# MainPCB_E.net
KiCad netlist of a schematic drawn in EAGLE
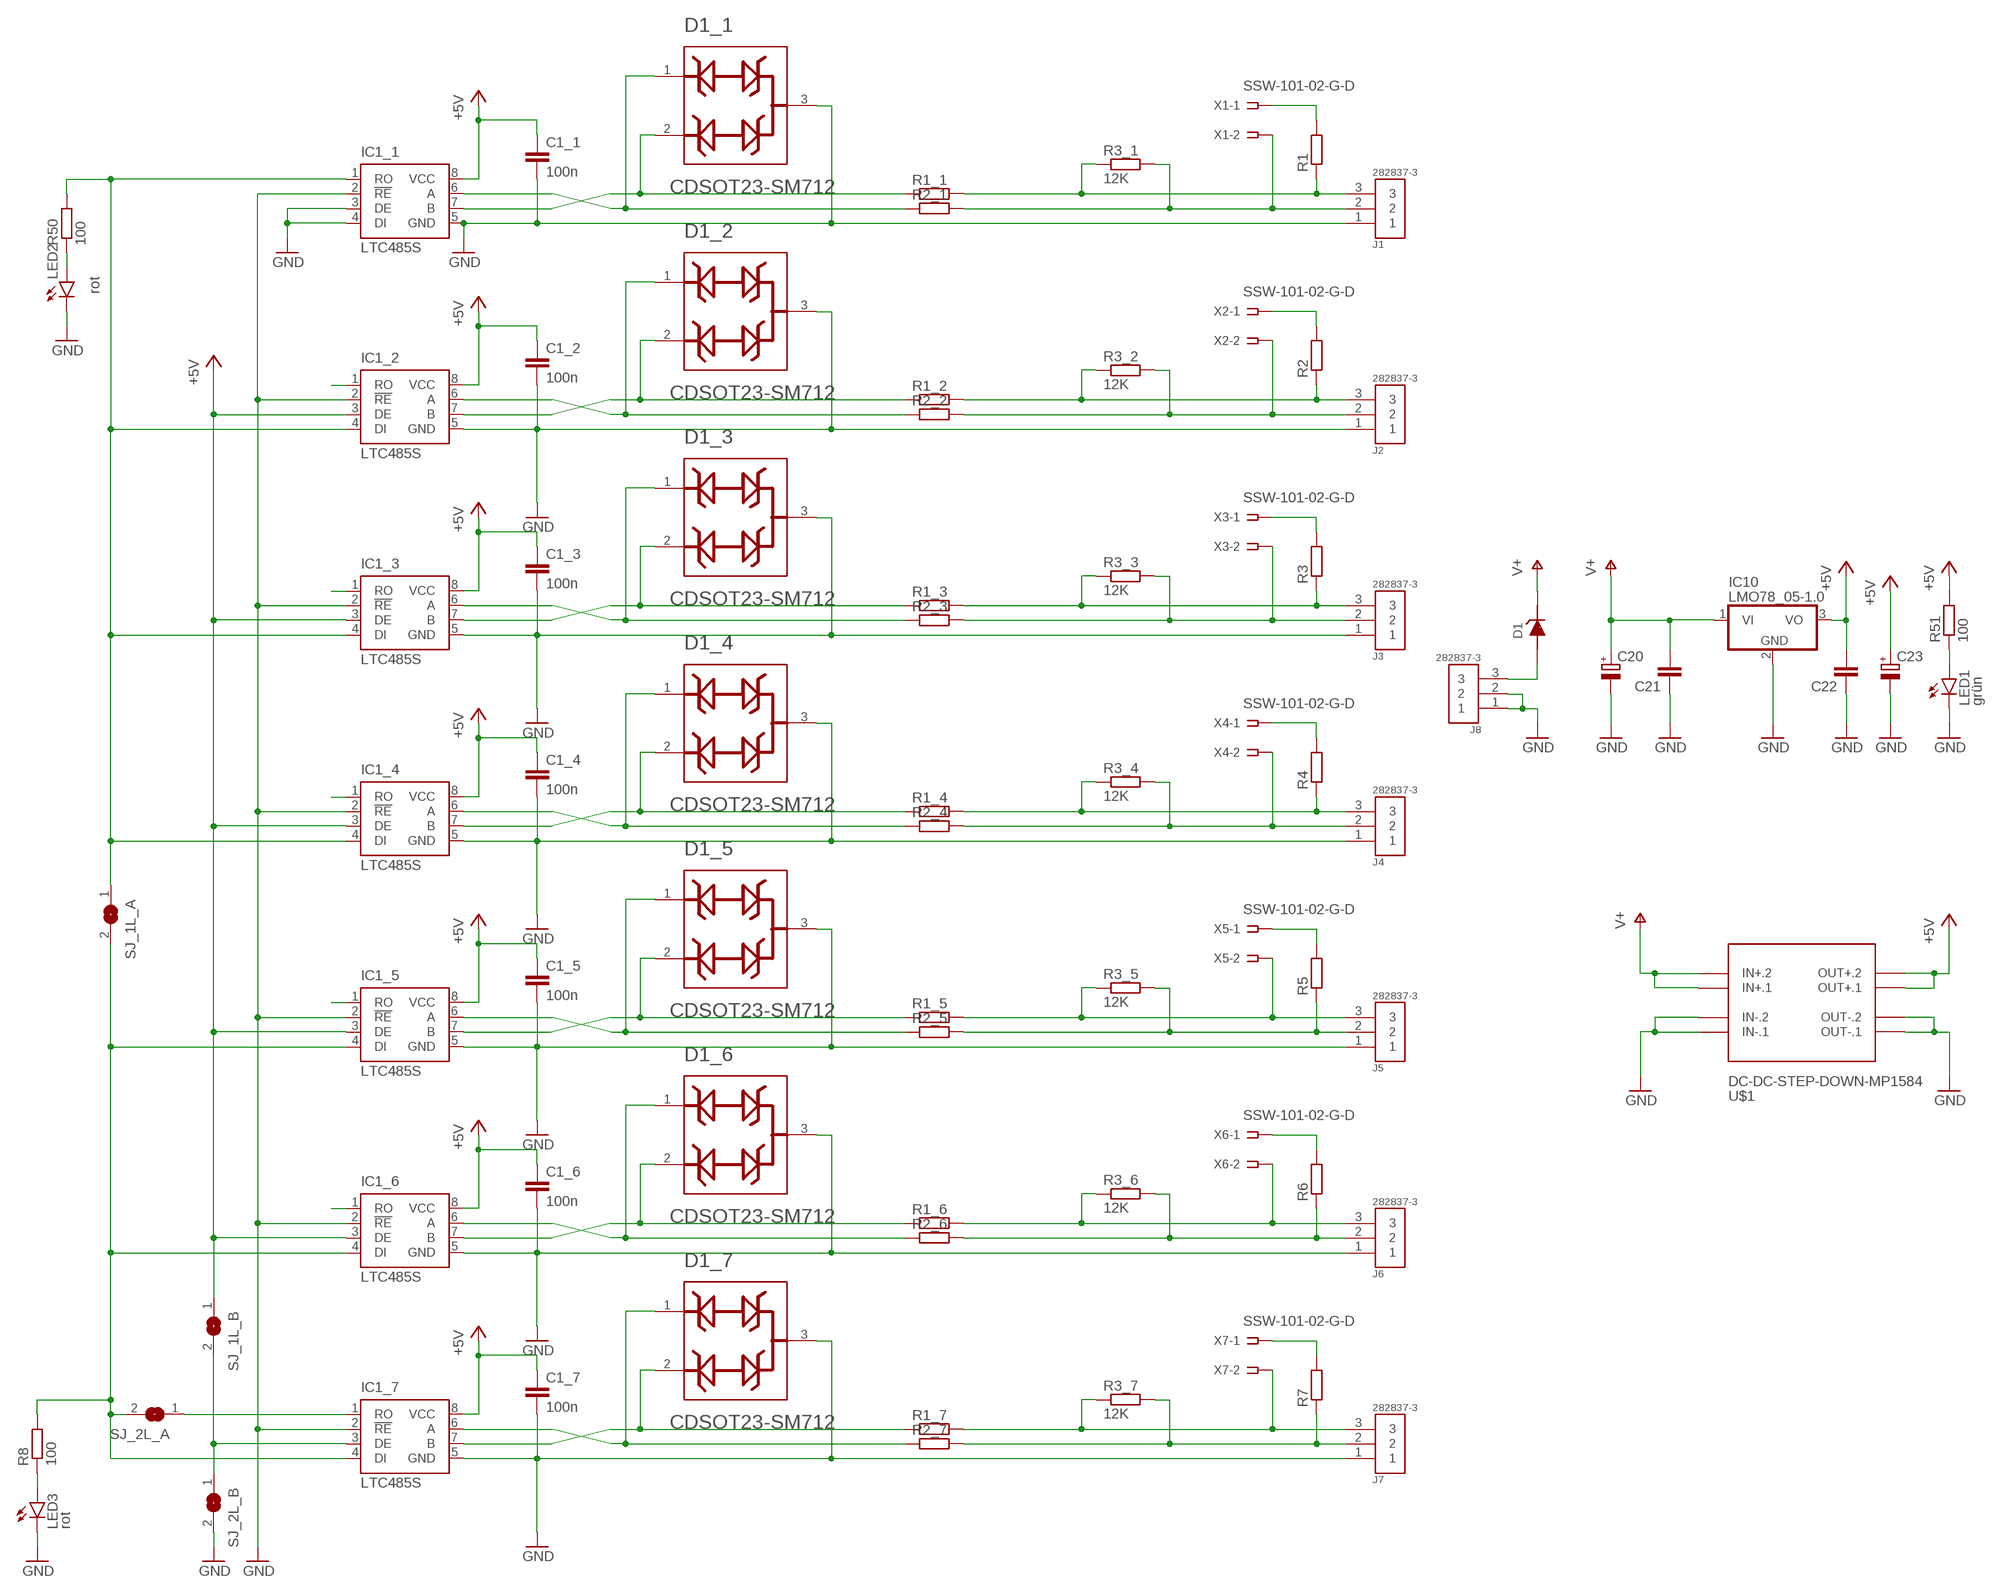
[diagram p0: schematic, sheet 1]

(export (version "E")
  (design (tool "Eeschema 10.0.6"))
  (components
    (comp (ref "C1_1")
      (value "100n")
      (footprint "eagle-import:C0603K")
      (libsource (lib "eagle-import") (part "C-EUC0603K"))
    )
    (comp (ref "C1_2")
      (value "100n")
      (footprint "eagle-import:C0603K")
      (libsource (lib "eagle-import") (part "C-EUC0603K"))
    )
    (comp (ref "C1_3")
      (value "100n")
      (footprint "eagle-import:C0603K")
      (libsource (lib "eagle-import") (part "C-EUC0603K"))
    )
    (comp (ref "C1_4")
      (value "100n")
      (footprint "eagle-import:C0603K")
      (libsource (lib "eagle-import") (part "C-EUC0603K"))
    )
    (comp (ref "C1_5")
      (value "100n")
      (footprint "eagle-import:C0603K")
      (libsource (lib "eagle-import") (part "C-EUC0603K"))
    )
    (comp (ref "C1_6")
      (value "100n")
      (footprint "eagle-import:C0603K")
      (libsource (lib "eagle-import") (part "C-EUC0603K"))
    )
    (comp (ref "C1_7")
      (value "100n")
      (footprint "eagle-import:C0603K")
      (libsource (lib "eagle-import") (part "C-EUC0603K"))
    )
    (comp (ref "C20")
      (value "CPOL-EUE5-8.5")
      (footprint "eagle-import:E5-8,5")
      (libsource (lib "eagle-import") (part "CPOL-EUE5-8.5"))
    )
    (comp (ref "C21")
      (value "C-EUC0805K")
      (footprint "eagle-import:C0805K")
      (libsource (lib "eagle-import") (part "C-EUC0805K"))
    )
    (comp (ref "C22")
      (value "C-EUC0805K")
      (footprint "eagle-import:C0805K")
      (libsource (lib "eagle-import") (part "C-EUC0805K"))
    )
    (comp (ref "C23")
      (value "CPOL-EUE5-8.5")
      (footprint "eagle-import:E5-8,5")
      (libsource (lib "eagle-import") (part "CPOL-EUE5-8.5"))
    )
    (comp (ref "D1")
      (value "ZMM")
      (footprint "eagle-import:MINIMELF")
      (libsource (lib "eagle-import") (part "ZMM"))
    )
    (comp (ref "D1_1")
      (value "BOURNS_INC._CDSOT23-SM712BOURNS_INC._CDSOT23-SM712_0_1")
      (footprint "eagle-import:BOURNS_INC._CDSOT23-SM712_1")
      (fields
        (field (name "DIGIKEY_PART_NUMBER") "CDSOT23-SM712CT-ND")
        (field (name "MF") "Bourns Inc.")
        (field (name "MOUSER_PART_NUMBER") "652-CDSOT23-SM712")
      )
      (libsource (lib "eagle-import") (part "BOURNS_INC._CDSOT23-SM712BOURNS_INC._CDSOT23-SM712_0_1"))
    )
    (comp (ref "D1_2")
      (value "BOURNS_INC._CDSOT23-SM712BOURNS_INC._CDSOT23-SM712_0_1")
      (footprint "eagle-import:BOURNS_INC._CDSOT23-SM712_1")
      (fields
        (field (name "DIGIKEY_PART_NUMBER") "CDSOT23-SM712CT-ND")
        (field (name "MF") "Bourns Inc.")
        (field (name "MOUSER_PART_NUMBER") "652-CDSOT23-SM712")
      )
      (libsource (lib "eagle-import") (part "BOURNS_INC._CDSOT23-SM712BOURNS_INC._CDSOT23-SM712_0_1"))
    )
    (comp (ref "D1_3")
      (value "BOURNS_INC._CDSOT23-SM712BOURNS_INC._CDSOT23-SM712_0_1")
      (footprint "eagle-import:BOURNS_INC._CDSOT23-SM712_1")
      (fields
        (field (name "DIGIKEY_PART_NUMBER") "CDSOT23-SM712CT-ND")
        (field (name "MF") "Bourns Inc.")
        (field (name "MOUSER_PART_NUMBER") "652-CDSOT23-SM712")
      )
      (libsource (lib "eagle-import") (part "BOURNS_INC._CDSOT23-SM712BOURNS_INC._CDSOT23-SM712_0_1"))
    )
    (comp (ref "D1_4")
      (value "BOURNS_INC._CDSOT23-SM712BOURNS_INC._CDSOT23-SM712_0_1")
      (footprint "eagle-import:BOURNS_INC._CDSOT23-SM712_1")
      (fields
        (field (name "DIGIKEY_PART_NUMBER") "CDSOT23-SM712CT-ND")
        (field (name "MF") "Bourns Inc.")
        (field (name "MOUSER_PART_NUMBER") "652-CDSOT23-SM712")
      )
      (libsource (lib "eagle-import") (part "BOURNS_INC._CDSOT23-SM712BOURNS_INC._CDSOT23-SM712_0_1"))
    )
    (comp (ref "D1_5")
      (value "BOURNS_INC._CDSOT23-SM712BOURNS_INC._CDSOT23-SM712_0_1")
      (footprint "eagle-import:BOURNS_INC._CDSOT23-SM712_1")
      (fields
        (field (name "DIGIKEY_PART_NUMBER") "CDSOT23-SM712CT-ND")
        (field (name "MF") "Bourns Inc.")
        (field (name "MOUSER_PART_NUMBER") "652-CDSOT23-SM712")
      )
      (libsource (lib "eagle-import") (part "BOURNS_INC._CDSOT23-SM712BOURNS_INC._CDSOT23-SM712_0_1"))
    )
    (comp (ref "D1_6")
      (value "BOURNS_INC._CDSOT23-SM712BOURNS_INC._CDSOT23-SM712_0_1")
      (footprint "eagle-import:BOURNS_INC._CDSOT23-SM712_1")
      (fields
        (field (name "DIGIKEY_PART_NUMBER") "CDSOT23-SM712CT-ND")
        (field (name "MF") "Bourns Inc.")
        (field (name "MOUSER_PART_NUMBER") "652-CDSOT23-SM712")
      )
      (libsource (lib "eagle-import") (part "BOURNS_INC._CDSOT23-SM712BOURNS_INC._CDSOT23-SM712_0_1"))
    )
    (comp (ref "D1_7")
      (value "BOURNS_INC._CDSOT23-SM712BOURNS_INC._CDSOT23-SM712_0_1")
      (footprint "eagle-import:BOURNS_INC._CDSOT23-SM712_1")
      (fields
        (field (name "DIGIKEY_PART_NUMBER") "CDSOT23-SM712CT-ND")
        (field (name "MF") "Bourns Inc.")
        (field (name "MOUSER_PART_NUMBER") "652-CDSOT23-SM712")
      )
      (libsource (lib "eagle-import") (part "BOURNS_INC._CDSOT23-SM712BOURNS_INC._CDSOT23-SM712_0_1"))
    )
    (comp (ref "IC1_1")
      (value "LTC485S")
      (footprint "eagle-import:SOIC8")
      (libsource (lib "eagle-import") (part "LTC485S"))
    )
    (comp (ref "IC1_2")
      (value "LTC485S")
      (footprint "eagle-import:SOIC8")
      (libsource (lib "eagle-import") (part "LTC485S"))
    )
    (comp (ref "IC1_3")
      (value "LTC485S")
      (footprint "eagle-import:SOIC8")
      (libsource (lib "eagle-import") (part "LTC485S"))
    )
    (comp (ref "IC1_4")
      (value "LTC485S")
      (footprint "eagle-import:SOIC8")
      (libsource (lib "eagle-import") (part "LTC485S"))
    )
    (comp (ref "IC1_5")
      (value "LTC485S")
      (footprint "eagle-import:SOIC8")
      (libsource (lib "eagle-import") (part "LTC485S"))
    )
    (comp (ref "IC1_6")
      (value "LTC485S")
      (footprint "eagle-import:SOIC8")
      (libsource (lib "eagle-import") (part "LTC485S"))
    )
    (comp (ref "IC1_7")
      (value "LTC485S")
      (footprint "eagle-import:SOIC8")
      (libsource (lib "eagle-import") (part "LTC485S"))
    )
    (comp (ref "IC10")
      (value "LMO78_05-1.0")
      (footprint "eagle-import:TO220V")
      (libsource (lib "eagle-import") (part "78TV15"))
    )
    (comp (ref "J1")
      (value "282837-3")
      (footprint "eagle-import:TE_282837-3")
      (fields (field (name "MANUFACTURER") "TE CONNECTIVITY"))
      (libsource (lib "eagle-import") (part "282837-3"))
    )
    (comp (ref "J2")
      (value "282837-3")
      (footprint "eagle-import:TE_282837-3")
      (fields (field (name "MANUFACTURER") "TE CONNECTIVITY"))
      (libsource (lib "eagle-import") (part "282837-3"))
    )
    (comp (ref "J3")
      (value "282837-3")
      (footprint "eagle-import:TE_282837-3")
      (fields (field (name "MANUFACTURER") "TE CONNECTIVITY"))
      (libsource (lib "eagle-import") (part "282837-3"))
    )
    (comp (ref "J4")
      (value "282837-3")
      (footprint "eagle-import:TE_282837-3")
      (fields (field (name "MANUFACTURER") "TE CONNECTIVITY"))
      (libsource (lib "eagle-import") (part "282837-3"))
    )
    (comp (ref "J5")
      (value "282837-3")
      (footprint "eagle-import:TE_282837-3")
      (fields (field (name "MANUFACTURER") "TE CONNECTIVITY"))
      (libsource (lib "eagle-import") (part "282837-3"))
    )
    (comp (ref "J6")
      (value "282837-3")
      (footprint "eagle-import:TE_282837-3")
      (fields (field (name "MANUFACTURER") "TE CONNECTIVITY"))
      (libsource (lib "eagle-import") (part "282837-3"))
    )
    (comp (ref "J7")
      (value "282837-3")
      (footprint "eagle-import:TE_282837-3")
      (fields (field (name "MANUFACTURER") "TE CONNECTIVITY"))
      (libsource (lib "eagle-import") (part "282837-3"))
    )
    (comp (ref "J8")
      (value "282837-3")
      (footprint "eagle-import:TE_282837-3")
      (fields (field (name "MANUFACTURER") "TE CONNECTIVITY"))
      (libsource (lib "eagle-import") (part "282837-3"))
    )
    (comp (ref "LED1")
      (value "grün")
      (footprint "eagle-import:LED5MM")
      (libsource (lib "eagle-import") (part "LED5MM"))
    )
    (comp (ref "LED2")
      (value "rot")
      (footprint "eagle-import:LED5MM")
      (libsource (lib "eagle-import") (part "LED5MM"))
    )
    (comp (ref "LED3")
      (value "rot")
      (footprint "eagle-import:LED5MM")
      (libsource (lib "eagle-import") (part "LED5MM"))
    )
    (comp (ref "R1")
      (value "R-EU_R1206")
      (footprint "eagle-import:R1206")
      (libsource (lib "eagle-import") (part "R-EU_R1206"))
    )
    (comp (ref "R1_1")
      (value "R-EU_R0805")
      (footprint "eagle-import:R0805")
      (libsource (lib "eagle-import") (part "R-EU_R0805"))
    )
    (comp (ref "R1_2")
      (value "R-EU_R0805")
      (footprint "eagle-import:R0805")
      (libsource (lib "eagle-import") (part "R-EU_R0805"))
    )
    (comp (ref "R1_3")
      (value "R-EU_R0805")
      (footprint "eagle-import:R0805")
      (libsource (lib "eagle-import") (part "R-EU_R0805"))
    )
    (comp (ref "R1_4")
      (value "R-EU_R0805")
      (footprint "eagle-import:R0805")
      (libsource (lib "eagle-import") (part "R-EU_R0805"))
    )
    (comp (ref "R1_5")
      (value "R-EU_R0805")
      (footprint "eagle-import:R0805")
      (libsource (lib "eagle-import") (part "R-EU_R0805"))
    )
    (comp (ref "R1_6")
      (value "R-EU_R0805")
      (footprint "eagle-import:R0805")
      (libsource (lib "eagle-import") (part "R-EU_R0805"))
    )
    (comp (ref "R1_7")
      (value "R-EU_R0805")
      (footprint "eagle-import:R0805")
      (libsource (lib "eagle-import") (part "R-EU_R0805"))
    )
    (comp (ref "R2")
      (value "R-EU_R1206")
      (footprint "eagle-import:R1206")
      (libsource (lib "eagle-import") (part "R-EU_R1206"))
    )
    (comp (ref "R2_1")
      (value "R-EU_R0805")
      (footprint "eagle-import:R0805")
      (libsource (lib "eagle-import") (part "R-EU_R0805"))
    )
    (comp (ref "R2_2")
      (value "R-EU_R0805")
      (footprint "eagle-import:R0805")
      (libsource (lib "eagle-import") (part "R-EU_R0805"))
    )
    (comp (ref "R2_3")
      (value "R-EU_R0805")
      (footprint "eagle-import:R0805")
      (libsource (lib "eagle-import") (part "R-EU_R0805"))
    )
    (comp (ref "R2_4")
      (value "R-EU_R0805")
      (footprint "eagle-import:R0805")
      (libsource (lib "eagle-import") (part "R-EU_R0805"))
    )
    (comp (ref "R2_5")
      (value "R-EU_R0805")
      (footprint "eagle-import:R0805")
      (libsource (lib "eagle-import") (part "R-EU_R0805"))
    )
    (comp (ref "R2_6")
      (value "R-EU_R0805")
      (footprint "eagle-import:R0805")
      (libsource (lib "eagle-import") (part "R-EU_R0805"))
    )
    (comp (ref "R2_7")
      (value "R-EU_R0805")
      (footprint "eagle-import:R0805")
      (libsource (lib "eagle-import") (part "R-EU_R0805"))
    )
    (comp (ref "R3")
      (value "R-EU_R1206")
      (footprint "eagle-import:R1206")
      (libsource (lib "eagle-import") (part "R-EU_R1206"))
    )
    (comp (ref "R3_1")
      (value "12K")
      (footprint "eagle-import:R0603")
      (libsource (lib "eagle-import") (part "R-EU_R0603"))
    )
    (comp (ref "R3_2")
      (value "12K")
      (footprint "eagle-import:R0603")
      (libsource (lib "eagle-import") (part "R-EU_R0603"))
    )
    (comp (ref "R3_3")
      (value "12K")
      (footprint "eagle-import:R0603")
      (libsource (lib "eagle-import") (part "R-EU_R0603"))
    )
    (comp (ref "R3_4")
      (value "12K")
      (footprint "eagle-import:R0603")
      (libsource (lib "eagle-import") (part "R-EU_R0603"))
    )
    (comp (ref "R3_5")
      (value "12K")
      (footprint "eagle-import:R0603")
      (libsource (lib "eagle-import") (part "R-EU_R0603"))
    )
    (comp (ref "R3_6")
      (value "12K")
      (footprint "eagle-import:R0603")
      (libsource (lib "eagle-import") (part "R-EU_R0603"))
    )
    (comp (ref "R3_7")
      (value "12K")
      (footprint "eagle-import:R0603")
      (libsource (lib "eagle-import") (part "R-EU_R0603"))
    )
    (comp (ref "R4")
      (value "R-EU_R1206")
      (footprint "eagle-import:R1206")
      (libsource (lib "eagle-import") (part "R-EU_R1206"))
    )
    (comp (ref "R5")
      (value "R-EU_R1206")
      (footprint "eagle-import:R1206")
      (libsource (lib "eagle-import") (part "R-EU_R1206"))
    )
    (comp (ref "R6")
      (value "R-EU_R1206")
      (footprint "eagle-import:R1206")
      (libsource (lib "eagle-import") (part "R-EU_R1206"))
    )
    (comp (ref "R7")
      (value "R-EU_R1206")
      (footprint "eagle-import:R1206")
      (libsource (lib "eagle-import") (part "R-EU_R1206"))
    )
    (comp (ref "R8")
      (value "100")
      (footprint "eagle-import:R0603")
      (libsource (lib "eagle-import") (part "R-EU_R0603"))
    )
    (comp (ref "R50")
      (value "100")
      (footprint "eagle-import:R0603")
      (libsource (lib "eagle-import") (part "R-EU_R0603"))
    )
    (comp (ref "R51")
      (value "100")
      (footprint "eagle-import:R0603")
      (libsource (lib "eagle-import") (part "R-EU_R0603"))
    )
    (comp (ref "SJ_1L_A")
      (value "SJ")
      (footprint "eagle-import:SJ")
      (libsource (lib "eagle-import") (part "SJ"))
    )
    (comp (ref "SJ_1L_B")
      (value "SJ")
      (footprint "eagle-import:SJ")
      (libsource (lib "eagle-import") (part "SJ"))
    )
    (comp (ref "SJ_2L_A")
      (value "SJ")
      (footprint "eagle-import:SJ")
      (libsource (lib "eagle-import") (part "SJ"))
    )
    (comp (ref "SJ_2L_B")
      (value "SJ")
      (footprint "eagle-import:SJ")
      (libsource (lib "eagle-import") (part "SJ"))
    )
    (comp (ref "U$1")
      (value "DC-DC-STEP-DOWN-MP1584")
      (footprint "eagle-import:DC-DC-STEP-DOWN-MP1584")
      (libsource (lib "eagle-import") (part "DC-DC-STEP-DOWN-MP1584"))
    )
    (comp (ref "X1")
      (value "SSW-101-02-G-D")
      (footprint "eagle-import:SSW-101-02-G-D")
      (fields (field (name "MF") "Samtec Inc."))
      (libsource (lib "eagle-import") (part "SSW-101-02-G-D"))
    )
    (comp (ref "X2")
      (value "SSW-101-02-G-D")
      (footprint "eagle-import:SSW-101-02-G-D")
      (fields (field (name "MF") "Samtec Inc."))
      (libsource (lib "eagle-import") (part "SSW-101-02-G-D"))
    )
    (comp (ref "X3")
      (value "SSW-101-02-G-D")
      (footprint "eagle-import:SSW-101-02-G-D")
      (fields (field (name "MF") "Samtec Inc."))
      (libsource (lib "eagle-import") (part "SSW-101-02-G-D"))
    )
    (comp (ref "X4")
      (value "SSW-101-02-G-D")
      (footprint "eagle-import:SSW-101-02-G-D")
      (fields (field (name "MF") "Samtec Inc."))
      (libsource (lib "eagle-import") (part "SSW-101-02-G-D"))
    )
    (comp (ref "X5")
      (value "SSW-101-02-G-D")
      (footprint "eagle-import:SSW-101-02-G-D")
      (fields (field (name "MF") "Samtec Inc."))
      (libsource (lib "eagle-import") (part "SSW-101-02-G-D"))
    )
    (comp (ref "X6")
      (value "SSW-101-02-G-D")
      (footprint "eagle-import:SSW-101-02-G-D")
      (fields (field (name "MF") "Samtec Inc."))
      (libsource (lib "eagle-import") (part "SSW-101-02-G-D"))
    )
    (comp (ref "X7")
      (value "SSW-101-02-G-D")
      (footprint "eagle-import:SSW-101-02-G-D")
      (fields (field (name "MF") "Samtec Inc."))
      (libsource (lib "eagle-import") (part "SSW-101-02-G-D"))
    )
  )
  (nets
    (net (code "1") (name "+5V") (class "Default")
      (node (ref "C1_1") (pin "1") (pinfunction "1_1") (pintype "passive"))
      (node (ref "C1_2") (pin "1") (pinfunction "1_1") (pintype "passive"))
      (node (ref "C1_3") (pin "1") (pinfunction "1_1") (pintype "passive"))
      (node (ref "C1_4") (pin "1") (pinfunction "1_1") (pintype "passive"))
      (node (ref "C1_5") (pin "1") (pinfunction "1_1") (pintype "passive"))
      (node (ref "C1_6") (pin "1") (pinfunction "1_1") (pintype "passive"))
      (node (ref "C1_7") (pin "1") (pinfunction "1_1") (pintype "passive"))
      (node (ref "C22") (pin "2") (pinfunction "2_2") (pintype "passive"))
      (node (ref "C23") (pin "+") (pinfunction "+_+") (pintype "passive"))
      (node (ref "IC10") (pin "3") (pinfunction "VO_3") (pintype "passive"))
      (node (ref "IC1_1") (pin "8") (pinfunction "VCC_8") (pintype "input"))
      (node (ref "IC1_2") (pin "3") (pinfunction "DE_3") (pintype "input"))
      (node (ref "IC1_2") (pin "8") (pinfunction "VCC_8") (pintype "input"))
      (node (ref "IC1_3") (pin "3") (pinfunction "DE_3") (pintype "input"))
      (node (ref "IC1_3") (pin "8") (pinfunction "VCC_8") (pintype "input"))
      (node (ref "IC1_4") (pin "3") (pinfunction "DE_3") (pintype "input"))
      (node (ref "IC1_4") (pin "8") (pinfunction "VCC_8") (pintype "input"))
      (node (ref "IC1_5") (pin "3") (pinfunction "DE_3") (pintype "input"))
      (node (ref "IC1_5") (pin "8") (pinfunction "VCC_8") (pintype "input"))
      (node (ref "IC1_6") (pin "3") (pinfunction "DE_3") (pintype "input"))
      (node (ref "IC1_6") (pin "8") (pinfunction "VCC_8") (pintype "input"))
      (node (ref "IC1_7") (pin "8") (pinfunction "VCC_8") (pintype "input"))
      (node (ref "R51") (pin "2") (pinfunction "2_2") (pintype "passive"))
      (node (ref "SJ_1L_B") (pin "1") (pinfunction "1_1") (pintype "passive"))
      (node (ref "U$1") (pin "OUT+.1") (pinfunction "OUT+.1_OUT+.1") (pintype "bidirectional"))
      (node (ref "U$1") (pin "OUT+.2") (pinfunction "OUT+.2_OUT+.2") (pintype "bidirectional"))
    )
    (net (code "2") (name "GND") (class "Default")
      (node (ref "C1_1") (pin "2") (pinfunction "2_2") (pintype "passive"))
      (node (ref "C1_2") (pin "2") (pinfunction "2_2") (pintype "passive"))
      (node (ref "C1_3") (pin "2") (pinfunction "2_2") (pintype "passive"))
      (node (ref "C1_4") (pin "2") (pinfunction "2_2") (pintype "passive"))
      (node (ref "C1_5") (pin "2") (pinfunction "2_2") (pintype "passive"))
      (node (ref "C1_6") (pin "2") (pinfunction "2_2") (pintype "passive"))
      (node (ref "C1_7") (pin "2") (pinfunction "2_2") (pintype "passive"))
      (node (ref "C20") (pin "-") (pinfunction "-_-") (pintype "passive"))
      (node (ref "C21") (pin "1") (pinfunction "1_1") (pintype "passive"))
      (node (ref "C22") (pin "1") (pinfunction "1_1") (pintype "passive"))
      (node (ref "C23") (pin "-") (pinfunction "-_-") (pintype "passive"))
      (node (ref "D1_1") (pin "3") (pinfunction "3_3") (pintype "passive"))
      (node (ref "D1_2") (pin "3") (pinfunction "3_3") (pintype "passive"))
      (node (ref "D1_3") (pin "3") (pinfunction "3_3") (pintype "passive"))
      (node (ref "D1_4") (pin "3") (pinfunction "3_3") (pintype "passive"))
      (node (ref "D1_5") (pin "3") (pinfunction "3_3") (pintype "passive"))
      (node (ref "D1_6") (pin "3") (pinfunction "3_3") (pintype "passive"))
      (node (ref "D1_7") (pin "3") (pinfunction "3_3") (pintype "passive"))
      (node (ref "IC10") (pin "2") (pinfunction "GND_2") (pintype "passive"))
      (node (ref "IC1_1") (pin "2") (pinfunction "~{RE}_2") (pintype "input"))
      (node (ref "IC1_1") (pin "3") (pinfunction "DE_3") (pintype "input"))
      (node (ref "IC1_1") (pin "4") (pinfunction "DI_4") (pintype "input"))
      (node (ref "IC1_1") (pin "5") (pinfunction "GND_5") (pintype "input"))
      (node (ref "IC1_2") (pin "2") (pinfunction "~{RE}_2") (pintype "input"))
      (node (ref "IC1_2") (pin "5") (pinfunction "GND_5") (pintype "input"))
      (node (ref "IC1_3") (pin "2") (pinfunction "~{RE}_2") (pintype "input"))
      (node (ref "IC1_3") (pin "5") (pinfunction "GND_5") (pintype "input"))
      (node (ref "IC1_4") (pin "2") (pinfunction "~{RE}_2") (pintype "input"))
      (node (ref "IC1_4") (pin "5") (pinfunction "GND_5") (pintype "input"))
      (node (ref "IC1_5") (pin "2") (pinfunction "~{RE}_2") (pintype "input"))
      (node (ref "IC1_5") (pin "5") (pinfunction "GND_5") (pintype "input"))
      (node (ref "IC1_6") (pin "2") (pinfunction "~{RE}_2") (pintype "input"))
      (node (ref "IC1_6") (pin "5") (pinfunction "GND_5") (pintype "input"))
      (node (ref "IC1_7") (pin "2") (pinfunction "~{RE}_2") (pintype "input"))
      (node (ref "IC1_7") (pin "5") (pinfunction "GND_5") (pintype "input"))
      (node (ref "J1") (pin "1") (pinfunction "1_1") (pintype "passive"))
      (node (ref "J2") (pin "1") (pinfunction "1_1") (pintype "passive"))
      (node (ref "J3") (pin "1") (pinfunction "1_1") (pintype "passive"))
      (node (ref "J4") (pin "1") (pinfunction "1_1") (pintype "passive"))
      (node (ref "J5") (pin "1") (pinfunction "1_1") (pintype "passive"))
      (node (ref "J6") (pin "1") (pinfunction "1_1") (pintype "passive"))
      (node (ref "J7") (pin "1") (pinfunction "1_1") (pintype "passive"))
      (node (ref "J8") (pin "1") (pinfunction "1_1") (pintype "passive"))
      (node (ref "J8") (pin "2") (pinfunction "2_2") (pintype "passive"))
      (node (ref "LED1") (pin "K") (pinfunction "C_K") (pintype "passive"))
      (node (ref "LED2") (pin "K") (pinfunction "C_K") (pintype "passive"))
      (node (ref "LED3") (pin "K") (pinfunction "C_K") (pintype "passive"))
      (node (ref "SJ_2L_B") (pin "2") (pinfunction "2_2") (pintype "passive"))
      (node (ref "U$1") (pin "IN-.1") (pinfunction "IN-.1_IN-.1") (pintype "bidirectional"))
      (node (ref "U$1") (pin "IN-.2") (pinfunction "IN-.2_IN-.2") (pintype "bidirectional"))
      (node (ref "U$1") (pin "OUT-.1") (pinfunction "OUT-.1_OUT-.1") (pintype "bidirectional"))
      (node (ref "U$1") (pin "OUT-.2") (pinfunction "OUT-.2_OUT-.2") (pintype "bidirectional"))
    )
    (net (code "3") (name "Net-(D1-PadA)") (class "Default")
      (node (ref "D1") (pin "A") (pinfunction "A_A") (pintype "passive"))
      (node (ref "J8") (pin "3") (pinfunction "3_3") (pintype "passive"))
    )
    (net (code "4") (name "Net-(IC1_1-A)") (class "Default")
      (node (ref "D1_1") (pin "1") (pinfunction "1_1") (pintype "passive"))
      (node (ref "IC1_1") (pin "6") (pinfunction "A_6") (pintype "bidirectional"))
      (node (ref "R2_1") (pin "1") (pinfunction "1_1") (pintype "passive"))
    )
    (net (code "5") (name "Net-(IC1_1-B)") (class "Default")
      (node (ref "D1_1") (pin "2") (pinfunction "2_2") (pintype "passive"))
      (node (ref "IC1_1") (pin "7") (pinfunction "B_7") (pintype "bidirectional"))
      (node (ref "R1_1") (pin "1") (pinfunction "1_1") (pintype "passive"))
    )
    (net (code "6") (name "Net-(IC1_1-RO)") (class "Default")
      (node (ref "IC1_1") (pin "1") (pinfunction "RO_1") (pintype "output"))
      (node (ref "IC1_2") (pin "4") (pinfunction "DI_4") (pintype "input"))
      (node (ref "IC1_3") (pin "4") (pinfunction "DI_4") (pintype "input"))
      (node (ref "IC1_4") (pin "4") (pinfunction "DI_4") (pintype "input"))
      (node (ref "R50") (pin "2") (pinfunction "2_2") (pintype "passive"))
      (node (ref "SJ_1L_A") (pin "1") (pinfunction "1_1") (pintype "passive"))
    )
    (net (code "7") (name "Net-(IC1_2-A)") (class "Default")
      (node (ref "D1_2") (pin "1") (pinfunction "1_1") (pintype "passive"))
      (node (ref "IC1_2") (pin "6") (pinfunction "A_6") (pintype "bidirectional"))
      (node (ref "R2_2") (pin "1") (pinfunction "1_1") (pintype "passive"))
    )
    (net (code "8") (name "Net-(IC1_2-B)") (class "Default")
      (node (ref "D1_2") (pin "2") (pinfunction "2_2") (pintype "passive"))
      (node (ref "IC1_2") (pin "7") (pinfunction "B_7") (pintype "bidirectional"))
      (node (ref "R1_2") (pin "1") (pinfunction "1_1") (pintype "passive"))
    )
    (net (code "9") (name "Net-(IC1_3-A)") (class "Default")
      (node (ref "D1_3") (pin "1") (pinfunction "1_1") (pintype "passive"))
      (node (ref "IC1_3") (pin "6") (pinfunction "A_6") (pintype "bidirectional"))
      (node (ref "R2_3") (pin "1") (pinfunction "1_1") (pintype "passive"))
    )
    (net (code "10") (name "Net-(IC1_3-B)") (class "Default")
      (node (ref "D1_3") (pin "2") (pinfunction "2_2") (pintype "passive"))
      (node (ref "IC1_3") (pin "7") (pinfunction "B_7") (pintype "bidirectional"))
      (node (ref "R1_3") (pin "1") (pinfunction "1_1") (pintype "passive"))
    )
    (net (code "11") (name "Net-(IC1_4-A)") (class "Default")
      (node (ref "D1_4") (pin "1") (pinfunction "1_1") (pintype "passive"))
      (node (ref "IC1_4") (pin "6") (pinfunction "A_6") (pintype "bidirectional"))
      (node (ref "R2_4") (pin "1") (pinfunction "1_1") (pintype "passive"))
    )
    (net (code "12") (name "Net-(IC1_4-B)") (class "Default")
      (node (ref "D1_4") (pin "2") (pinfunction "2_2") (pintype "passive"))
      (node (ref "IC1_4") (pin "7") (pinfunction "B_7") (pintype "bidirectional"))
      (node (ref "R1_4") (pin "1") (pinfunction "1_1") (pintype "passive"))
    )
    (net (code "13") (name "Net-(IC1_5-A)") (class "Default")
      (node (ref "D1_5") (pin "1") (pinfunction "1_1") (pintype "passive"))
      (node (ref "IC1_5") (pin "6") (pinfunction "A_6") (pintype "bidirectional"))
      (node (ref "R2_5") (pin "1") (pinfunction "1_1") (pintype "passive"))
    )
    (net (code "14") (name "Net-(IC1_5-B)") (class "Default")
      (node (ref "D1_5") (pin "2") (pinfunction "2_2") (pintype "passive"))
      (node (ref "IC1_5") (pin "7") (pinfunction "B_7") (pintype "bidirectional"))
      (node (ref "R1_5") (pin "1") (pinfunction "1_1") (pintype "passive"))
    )
    (net (code "15") (name "Net-(IC1_5-DI)") (class "Default")
      (node (ref "IC1_5") (pin "4") (pinfunction "DI_4") (pintype "input"))
      (node (ref "IC1_6") (pin "4") (pinfunction "DI_4") (pintype "input"))
      (node (ref "IC1_7") (pin "4") (pinfunction "DI_4") (pintype "input"))
      (node (ref "R8") (pin "2") (pinfunction "2_2") (pintype "passive"))
      (node (ref "SJ_1L_A") (pin "2") (pinfunction "2_2") (pintype "passive"))
      (node (ref "SJ_2L_A") (pin "2") (pinfunction "2_2") (pintype "passive"))
    )
    (net (code "16") (name "Net-(IC1_6-A)") (class "Default")
      (node (ref "D1_6") (pin "1") (pinfunction "1_1") (pintype "passive"))
      (node (ref "IC1_6") (pin "6") (pinfunction "A_6") (pintype "bidirectional"))
      (node (ref "R2_6") (pin "1") (pinfunction "1_1") (pintype "passive"))
    )
    (net (code "17") (name "Net-(IC1_6-B)") (class "Default")
      (node (ref "D1_6") (pin "2") (pinfunction "2_2") (pintype "passive"))
      (node (ref "IC1_6") (pin "7") (pinfunction "B_7") (pintype "bidirectional"))
      (node (ref "R1_6") (pin "1") (pinfunction "1_1") (pintype "passive"))
    )
    (net (code "18") (name "Net-(IC1_7-A)") (class "Default")
      (node (ref "D1_7") (pin "1") (pinfunction "1_1") (pintype "passive"))
      (node (ref "IC1_7") (pin "6") (pinfunction "A_6") (pintype "bidirectional"))
      (node (ref "R2_7") (pin "1") (pinfunction "1_1") (pintype "passive"))
    )
    (net (code "19") (name "Net-(IC1_7-B)") (class "Default")
      (node (ref "D1_7") (pin "2") (pinfunction "2_2") (pintype "passive"))
      (node (ref "IC1_7") (pin "7") (pinfunction "B_7") (pintype "bidirectional"))
      (node (ref "R1_7") (pin "1") (pinfunction "1_1") (pintype "passive"))
    )
    (net (code "20") (name "Net-(IC1_7-DE)") (class "Default")
      (node (ref "IC1_7") (pin "3") (pinfunction "DE_3") (pintype "input"))
      (node (ref "SJ_1L_B") (pin "2") (pinfunction "2_2") (pintype "passive"))
      (node (ref "SJ_2L_B") (pin "1") (pinfunction "1_1") (pintype "passive"))
    )
    (net (code "21") (name "Net-(IC1_7-RO)") (class "Default")
      (node (ref "IC1_7") (pin "1") (pinfunction "RO_1") (pintype "output"))
      (node (ref "SJ_2L_A") (pin "1") (pinfunction "1_1") (pintype "passive"))
    )
    (net (code "22") (name "Net-(J1-Pad3)") (class "Default")
      (node (ref "J1") (pin "3") (pinfunction "3_3") (pintype "passive"))
      (node (ref "R1") (pin "1") (pinfunction "1_1") (pintype "passive"))
      (node (ref "R1_1") (pin "2") (pinfunction "2_2") (pintype "passive"))
      (node (ref "R3_1") (pin "1") (pinfunction "1_1") (pintype "passive"))
    )
    (net (code "23") (name "Net-(J2-Pad3)") (class "Default")
      (node (ref "J2") (pin "3") (pinfunction "3_3") (pintype "passive"))
      (node (ref "R1_2") (pin "2") (pinfunction "2_2") (pintype "passive"))
      (node (ref "R2") (pin "1") (pinfunction "1_1") (pintype "passive"))
      (node (ref "R3_2") (pin "1") (pinfunction "1_1") (pintype "passive"))
    )
    (net (code "24") (name "Net-(J3-Pad3)") (class "Default")
      (node (ref "J3") (pin "3") (pinfunction "3_3") (pintype "passive"))
      (node (ref "R1_3") (pin "2") (pinfunction "2_2") (pintype "passive"))
      (node (ref "R3") (pin "1") (pinfunction "1_1") (pintype "passive"))
      (node (ref "R3_3") (pin "1") (pinfunction "1_1") (pintype "passive"))
    )
    (net (code "25") (name "Net-(J4-Pad3)") (class "Default")
      (node (ref "J4") (pin "3") (pinfunction "3_3") (pintype "passive"))
      (node (ref "R1_4") (pin "2") (pinfunction "2_2") (pintype "passive"))
      (node (ref "R3_4") (pin "1") (pinfunction "1_1") (pintype "passive"))
      (node (ref "R4") (pin "1") (pinfunction "1_1") (pintype "passive"))
    )
    (net (code "26") (name "Net-(J5-Pad2)") (class "Default")
      (node (ref "J5") (pin "2") (pinfunction "2_2") (pintype "passive"))
      (node (ref "R2_5") (pin "2") (pinfunction "2_2") (pintype "passive"))
      (node (ref "R3_5") (pin "2") (pinfunction "2_2") (pintype "passive"))
      (node (ref "R5") (pin "1") (pinfunction "1_1") (pintype "passive"))
    )
    (net (code "27") (name "Net-(J6-Pad2)") (class "Default")
      (node (ref "J6") (pin "2") (pinfunction "2_2") (pintype "passive"))
      (node (ref "R2_6") (pin "2") (pinfunction "2_2") (pintype "passive"))
      (node (ref "R3_6") (pin "2") (pinfunction "2_2") (pintype "passive"))
      (node (ref "R6") (pin "1") (pinfunction "1_1") (pintype "passive"))
    )
    (net (code "28") (name "Net-(J7-Pad2)") (class "Default")
      (node (ref "J7") (pin "2") (pinfunction "2_2") (pintype "passive"))
      (node (ref "R2_7") (pin "2") (pinfunction "2_2") (pintype "passive"))
      (node (ref "R3_7") (pin "2") (pinfunction "2_2") (pintype "passive"))
      (node (ref "R7") (pin "1") (pinfunction "1_1") (pintype "passive"))
    )
    (net (code "29") (name "Net-(LED1-PadA)") (class "Default")
      (node (ref "LED1") (pin "A") (pinfunction "A_A") (pintype "passive"))
      (node (ref "R51") (pin "1") (pinfunction "1_1") (pintype "passive"))
    )
    (net (code "30") (name "Net-(LED2-PadA)") (class "Default")
      (node (ref "LED2") (pin "A") (pinfunction "A_A") (pintype "passive"))
      (node (ref "R50") (pin "1") (pinfunction "1_1") (pintype "passive"))
    )
    (net (code "31") (name "Net-(LED3-PadA)") (class "Default")
      (node (ref "LED3") (pin "A") (pinfunction "A_A") (pintype "passive"))
      (node (ref "R8") (pin "1") (pinfunction "1_1") (pintype "passive"))
    )
    (net (code "32") (name "Net-(R1-Pad2)") (class "Default")
      (node (ref "R1") (pin "2") (pinfunction "2_2") (pintype "passive"))
      (node (ref "X1") (pin "1") (pinfunction "1_1") (pintype "passive"))
    )
    (net (code "33") (name "Net-(R2-Pad2)") (class "Default")
      (node (ref "R2") (pin "2") (pinfunction "2_2") (pintype "passive"))
      (node (ref "X2") (pin "1") (pinfunction "1_1") (pintype "passive"))
    )
    (net (code "34") (name "Net-(R3-Pad2)") (class "Default")
      (node (ref "R3") (pin "2") (pinfunction "2_2") (pintype "passive"))
      (node (ref "X3") (pin "1") (pinfunction "1_1") (pintype "passive"))
    )
    (net (code "35") (name "Net-(R4-Pad2)") (class "Default")
      (node (ref "R4") (pin "2") (pinfunction "2_2") (pintype "passive"))
      (node (ref "X4") (pin "1") (pinfunction "1_1") (pintype "passive"))
    )
    (net (code "36") (name "Net-(R5-Pad2)") (class "Default")
      (node (ref "R5") (pin "2") (pinfunction "2_2") (pintype "passive"))
      (node (ref "X5") (pin "1") (pinfunction "1_1") (pintype "passive"))
    )
    (net (code "37") (name "Net-(R6-Pad2)") (class "Default")
      (node (ref "R6") (pin "2") (pinfunction "2_2") (pintype "passive"))
      (node (ref "X6") (pin "1") (pinfunction "1_1") (pintype "passive"))
    )
    (net (code "38") (name "Net-(R7-Pad2)") (class "Default")
      (node (ref "R7") (pin "2") (pinfunction "2_2") (pintype "passive"))
      (node (ref "X7") (pin "1") (pinfunction "1_1") (pintype "passive"))
    )
    (net (code "39") (name "Net-(X1B-1)") (class "Default")
      (node (ref "J1") (pin "2") (pinfunction "2_2") (pintype "passive"))
      (node (ref "R2_1") (pin "2") (pinfunction "2_2") (pintype "passive"))
      (node (ref "R3_1") (pin "2") (pinfunction "2_2") (pintype "passive"))
      (node (ref "X1") (pin "2") (pinfunction "1_2") (pintype "passive"))
    )
    (net (code "40") (name "Net-(X2B-1)") (class "Default")
      (node (ref "J2") (pin "2") (pinfunction "2_2") (pintype "passive"))
      (node (ref "R2_2") (pin "2") (pinfunction "2_2") (pintype "passive"))
      (node (ref "R3_2") (pin "2") (pinfunction "2_2") (pintype "passive"))
      (node (ref "X2") (pin "2") (pinfunction "1_2") (pintype "passive"))
    )
    (net (code "41") (name "Net-(X3B-1)") (class "Default")
      (node (ref "J3") (pin "2") (pinfunction "2_2") (pintype "passive"))
      (node (ref "R2_3") (pin "2") (pinfunction "2_2") (pintype "passive"))
      (node (ref "R3_3") (pin "2") (pinfunction "2_2") (pintype "passive"))
      (node (ref "X3") (pin "2") (pinfunction "1_2") (pintype "passive"))
    )
    (net (code "42") (name "Net-(X4B-1)") (class "Default")
      (node (ref "J4") (pin "2") (pinfunction "2_2") (pintype "passive"))
      (node (ref "R2_4") (pin "2") (pinfunction "2_2") (pintype "passive"))
      (node (ref "R3_4") (pin "2") (pinfunction "2_2") (pintype "passive"))
      (node (ref "X4") (pin "2") (pinfunction "1_2") (pintype "passive"))
    )
    (net (code "43") (name "Net-(X5B-1)") (class "Default")
      (node (ref "J5") (pin "3") (pinfunction "3_3") (pintype "passive"))
      (node (ref "R1_5") (pin "2") (pinfunction "2_2") (pintype "passive"))
      (node (ref "R3_5") (pin "1") (pinfunction "1_1") (pintype "passive"))
      (node (ref "X5") (pin "2") (pinfunction "1_2") (pintype "passive"))
    )
    (net (code "44") (name "Net-(X6B-1)") (class "Default")
      (node (ref "J6") (pin "3") (pinfunction "3_3") (pintype "passive"))
      (node (ref "R1_6") (pin "2") (pinfunction "2_2") (pintype "passive"))
      (node (ref "R3_6") (pin "1") (pinfunction "1_1") (pintype "passive"))
      (node (ref "X6") (pin "2") (pinfunction "1_2") (pintype "passive"))
    )
    (net (code "45") (name "Net-(X7B-1)") (class "Default")
      (node (ref "J7") (pin "3") (pinfunction "3_3") (pintype "passive"))
      (node (ref "R1_7") (pin "2") (pinfunction "2_2") (pintype "passive"))
      (node (ref "R3_7") (pin "1") (pinfunction "1_1") (pintype "passive"))
      (node (ref "X7") (pin "2") (pinfunction "1_2") (pintype "passive"))
    )
    (net (code "46") (name "V+") (class "Default")
      (node (ref "C20") (pin "+") (pinfunction "+_+") (pintype "passive"))
      (node (ref "C21") (pin "2") (pinfunction "2_2") (pintype "passive"))
      (node (ref "D1") (pin "C") (pinfunction "K_C") (pintype "passive"))
      (node (ref "IC10") (pin "1") (pinfunction "VI_1") (pintype "input"))
      (node (ref "U$1") (pin "IN+.1") (pinfunction "IN+.1_IN+.1") (pintype "bidirectional"))
      (node (ref "U$1") (pin "IN+.2") (pinfunction "IN+.2_IN+.2") (pintype "bidirectional"))
    )
    (net (code "47") (name "unconnected-(IC1_2-RO-Pad1)") (class "Default")
      (node (ref "IC1_2") (pin "1") (pinfunction "RO_1") (pintype "output"))
    )
    (net (code "48") (name "unconnected-(IC1_3-RO-Pad1)") (class "Default")
      (node (ref "IC1_3") (pin "1") (pinfunction "RO_1") (pintype "output"))
    )
    (net (code "49") (name "unconnected-(IC1_4-RO-Pad1)") (class "Default")
      (node (ref "IC1_4") (pin "1") (pinfunction "RO_1") (pintype "output"))
    )
    (net (code "50") (name "unconnected-(IC1_5-RO-Pad1)") (class "Default")
      (node (ref "IC1_5") (pin "1") (pinfunction "RO_1") (pintype "output"))
    )
    (net (code "51") (name "unconnected-(IC1_6-RO-Pad1)") (class "Default")
      (node (ref "IC1_6") (pin "1") (pinfunction "RO_1") (pintype "output"))
    )
  )
)
